# adc12.net
KiCad netlist of a schematic drawn in EAGLE
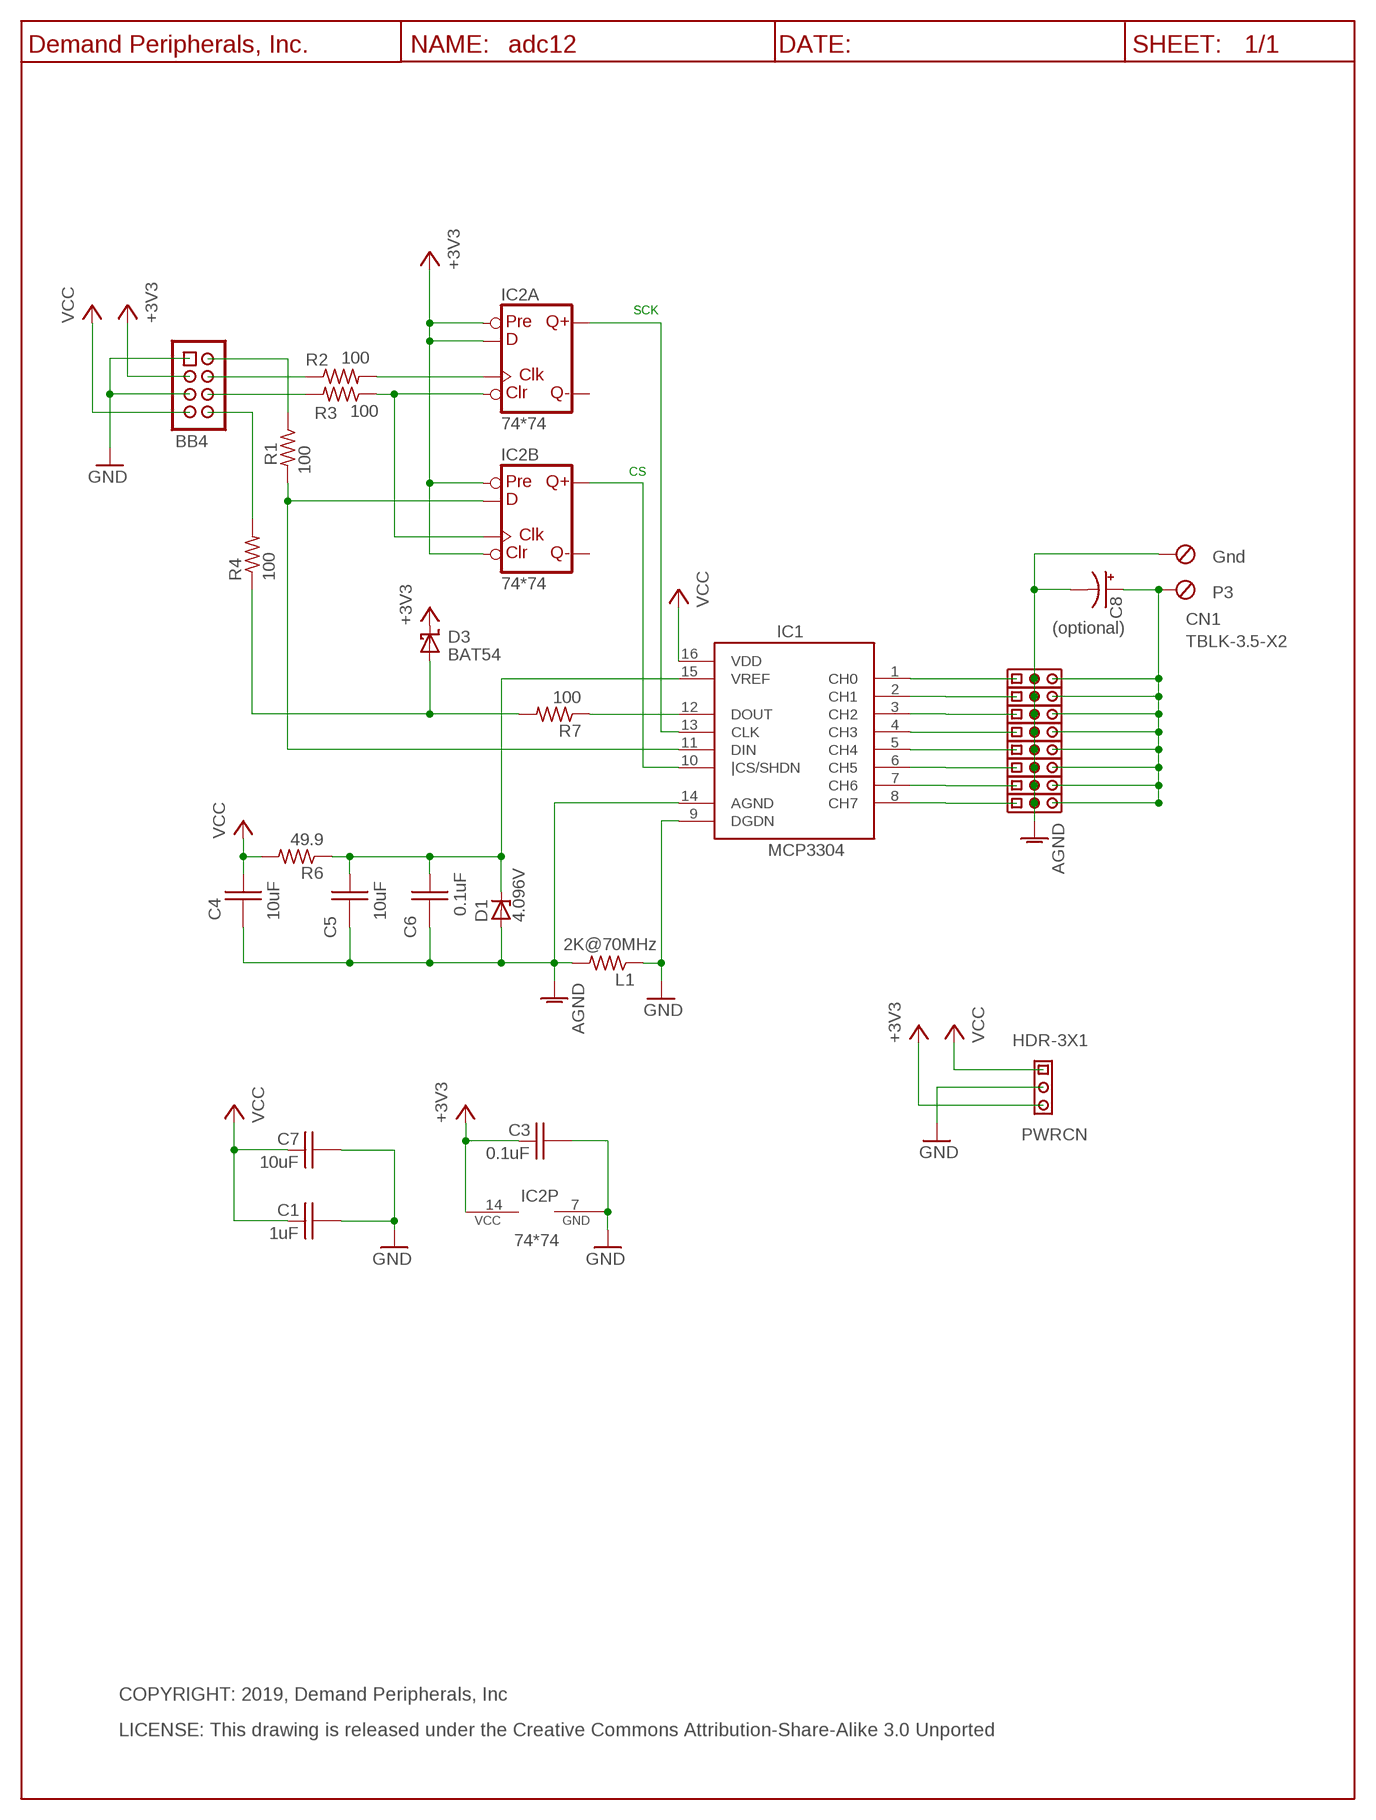
[diagram p0: schematic, sheet 1]

(export (version "E")
  (design (tool "Eeschema 10.0.6"))
  (components
    (comp (ref "BB4")
      (value "BB4_CON")
      (footprint "eagle-import:HDR-4X2")
      (libsource (lib "eagle-import") (part "HDR-4X2-SHR"))
    )
    (comp (ref "C1")
      (value "1uF")
      (footprint "eagle-import:C0603")
      (libsource (lib "eagle-import") (part "C1.0UF_C0603"))
    )
    (comp (ref "C3")
      (value "0.1uF")
      (footprint "eagle-import:C0603")
      (libsource (lib "eagle-import") (part "C0.1UF_C0603"))
    )
    (comp (ref "C4")
      (value "10uF")
      (footprint "eagle-import:C0805")
      (libsource (lib "eagle-import") (part "C10UF35V_C0805"))
    )
    (comp (ref "C5")
      (value "10uF")
      (footprint "eagle-import:C0805")
      (libsource (lib "eagle-import") (part "C10UF35V_C0805"))
    )
    (comp (ref "C6")
      (value "0.1uF")
      (footprint "eagle-import:C0603")
      (libsource (lib "eagle-import") (part "C0.1UF_C0603"))
    )
    (comp (ref "C7")
      (value "10uF")
      (footprint "eagle-import:C0805")
      (libsource (lib "eagle-import") (part "C10UF35V_C0805"))
    )
    (comp (ref "C8")
      (value "C100UF_E3.5-8")
      (footprint "eagle-import:E3.5-8")
      (libsource (lib "eagle-import") (part "C100UF_E3.5-8"))
    )
    (comp (ref "CN1")
      (value "TBLK-3.5-X2")
      (footprint "eagle-import:TBLK-3.5-X2")
      (libsource (lib "eagle-import") (part "TBLK-3.5-X2"))
    )
    (comp (ref "D1")
      (value "4.096V")
      (footprint "eagle-import:SOT23")
      (libsource (lib "eagle-import") (part "LM4040"))
    )
    (comp (ref "D3")
      (value "BAT54")
      (footprint "eagle-import:SOT23")
      (libsource (lib "eagle-import") (part "BAT54"))
    )
    (comp (ref "IC1")
      (value "MCP3304")
      (footprint "eagle-import:SO16")
      (libsource (lib "eagle-import") (part "MCP3304"))
    )
    (comp (ref "IC2")
      (value "74*74")
      (footprint "eagle-import:SO14")
      (libsource (lib "eagle-import") (part "74AHC74SS"))
    )
    (comp (ref "L1")
      (value "2K@70MHz")
      (footprint "eagle-import:R0805")
      (libsource (lib "eagle-import") (part "L2K70MHZR0805"))
    )
    (comp (ref "PWRCN")
      (value "HDR-3X1")
      (footprint "eagle-import:HDR-3X1")
      (libsource (lib "eagle-import") (part "HDR-3X1"))
    )
    (comp (ref "R1")
      (value "100")
      (footprint "eagle-import:R0603")
      (libsource (lib "eagle-import") (part "R100_R0603"))
    )
    (comp (ref "R2")
      (value "100")
      (footprint "eagle-import:R0603")
      (libsource (lib "eagle-import") (part "R100_R0603"))
    )
    (comp (ref "R3")
      (value "100")
      (footprint "eagle-import:R0603")
      (libsource (lib "eagle-import") (part "R100_R0603"))
    )
    (comp (ref "R4")
      (value "100")
      (footprint "eagle-import:R0603")
      (libsource (lib "eagle-import") (part "R100_R0603"))
    )
    (comp (ref "R6")
      (value "49.9")
      (footprint "eagle-import:R0603")
      (libsource (lib "eagle-import") (part "R49.9R0603"))
    )
    (comp (ref "R7")
      (value "100")
      (footprint "eagle-import:R0603")
      (libsource (lib "eagle-import") (part "R100_R0603"))
    )
    (comp (ref "U$3")
      (value "DP_FRAME_P")
      (footprint "eagle-import:LETTER_P")
      (libsource (lib "eagle-import") (part "DP_FRAME_P"))
    )
    (comp (ref "U$6")
      (value "HDR-3X1")
      (footprint "eagle-import:HDR-3X1")
      (libsource (lib "eagle-import") (part "HDR-3X1"))
    )
    (comp (ref "U$7")
      (value "HDR-3X1")
      (footprint "eagle-import:HDR-3X1")
      (libsource (lib "eagle-import") (part "HDR-3X1"))
    )
    (comp (ref "U$8")
      (value "HDR-3X1")
      (footprint "eagle-import:HDR-3X1")
      (libsource (lib "eagle-import") (part "HDR-3X1"))
    )
    (comp (ref "U$9")
      (value "HDR-3X1")
      (footprint "eagle-import:HDR-3X1")
      (libsource (lib "eagle-import") (part "HDR-3X1"))
    )
    (comp (ref "U$10")
      (value "HDR-3X1")
      (footprint "eagle-import:HDR-3X1")
      (libsource (lib "eagle-import") (part "HDR-3X1"))
    )
    (comp (ref "U$11")
      (value "HDR-3X1")
      (footprint "eagle-import:HDR-3X1")
      (libsource (lib "eagle-import") (part "HDR-3X1"))
    )
    (comp (ref "U$12")
      (value "HDR-3X1")
      (footprint "eagle-import:HDR-3X1")
      (libsource (lib "eagle-import") (part "HDR-3X1"))
    )
    (comp (ref "U$13")
      (value "HDR-3X1")
      (footprint "eagle-import:HDR-3X1")
      (libsource (lib "eagle-import") (part "HDR-3X1"))
    )
  )
  (nets
    (net (code "1") (name "+3V3") (class "Default")
      (node (ref "BB4") (pin "3") (pinfunction "3_3") (pintype "passive"))
      (node (ref "C3") (pin "1") (pinfunction "1_1") (pintype "passive"))
      (node (ref "D3") (pin "3") (pinfunction "CC_3") (pintype "passive"))
      (node (ref "IC2") (pin "10") (pinfunction "PRE_10") (pintype "input"))
      (node (ref "IC2") (pin "13") (pinfunction "CLR_13") (pintype "input"))
      (node (ref "IC2") (pin "14") (pinfunction "VCC_14") (pintype "power_in"))
      (node (ref "IC2") (pin "2") (pinfunction "D_2") (pintype "input"))
      (node (ref "IC2") (pin "4") (pinfunction "PRE_4") (pintype "input"))
      (node (ref "PWRCN") (pin "3") (pinfunction "3_3") (pintype "passive"))
    )
    (net (code "2") (name "AGND") (class "Default")
      (node (ref "C4") (pin "2") (pinfunction "2_2") (pintype "passive"))
      (node (ref "C5") (pin "2") (pinfunction "2_2") (pintype "passive"))
      (node (ref "C6") (pin "2") (pinfunction "2_2") (pintype "passive"))
      (node (ref "C8") (pin "-") (pinfunction "-_-") (pintype "passive"))
      (node (ref "CN1") (pin "1") (pinfunction "KL_1") (pintype "passive"))
      (node (ref "D1") (pin "2") (pinfunction "A_2") (pintype "passive"))
      (node (ref "IC1") (pin "14") (pinfunction "AGND_14") (pintype "bidirectional"))
      (node (ref "L1") (pin "2") (pinfunction "2_2") (pintype "passive"))
      (node (ref "U$10") (pin "2") (pinfunction "2_2") (pintype "passive"))
      (node (ref "U$11") (pin "2") (pinfunction "2_2") (pintype "passive"))
      (node (ref "U$12") (pin "2") (pinfunction "2_2") (pintype "passive"))
      (node (ref "U$13") (pin "2") (pinfunction "2_2") (pintype "passive"))
      (node (ref "U$6") (pin "2") (pinfunction "2_2") (pintype "passive"))
      (node (ref "U$7") (pin "2") (pinfunction "2_2") (pintype "passive"))
      (node (ref "U$8") (pin "2") (pinfunction "2_2") (pintype "passive"))
      (node (ref "U$9") (pin "2") (pinfunction "2_2") (pintype "passive"))
    )
    (net (code "3") (name "GND") (class "Default")
      (node (ref "BB4") (pin "1") (pinfunction "1_1") (pintype "passive"))
      (node (ref "BB4") (pin "5") (pinfunction "5_5") (pintype "passive"))
      (node (ref "C1") (pin "2") (pinfunction "2_2") (pintype "passive"))
      (node (ref "C3") (pin "2") (pinfunction "2_2") (pintype "passive"))
      (node (ref "C7") (pin "2") (pinfunction "2_2") (pintype "passive"))
      (node (ref "IC1") (pin "9") (pinfunction "DGDN_9") (pintype "bidirectional"))
      (node (ref "IC2") (pin "7") (pinfunction "GND_7") (pintype "power_in"))
      (node (ref "L1") (pin "1") (pinfunction "1_1") (pintype "passive"))
      (node (ref "PWRCN") (pin "2") (pinfunction "2_2") (pintype "passive"))
    )
    (net (code "4") (name "Net-(BB4-Pad2)") (class "Default")
      (node (ref "BB4") (pin "2") (pinfunction "2_2") (pintype "passive"))
      (node (ref "R1") (pin "1") (pinfunction "1_1") (pintype "passive"))
    )
    (net (code "5") (name "Net-(BB4-Pad4)") (class "Default")
      (node (ref "BB4") (pin "4") (pinfunction "4_4") (pintype "passive"))
      (node (ref "R2") (pin "1") (pinfunction "1_1") (pintype "passive"))
    )
    (net (code "6") (name "Net-(BB4-Pad6)") (class "Default")
      (node (ref "BB4") (pin "6") (pinfunction "6_6") (pintype "passive"))
      (node (ref "R3") (pin "2") (pinfunction "2_2") (pintype "passive"))
    )
    (net (code "7") (name "Net-(BB4-Pad8)") (class "Default")
      (node (ref "BB4") (pin "8") (pinfunction "8_8") (pintype "passive"))
      (node (ref "R4") (pin "2") (pinfunction "2_2") (pintype "passive"))
    )
    (net (code "8") (name "Net-(CN1-KL1)") (class "Default")
      (node (ref "C8") (pin "+") (pinfunction "+_+") (pintype "passive"))
      (node (ref "CN1") (pin "2") (pinfunction "KL1_2") (pintype "passive"))
      (node (ref "U$10") (pin "3") (pinfunction "3_3") (pintype "passive"))
      (node (ref "U$11") (pin "3") (pinfunction "3_3") (pintype "passive"))
      (node (ref "U$12") (pin "3") (pinfunction "3_3") (pintype "passive"))
      (node (ref "U$13") (pin "3") (pinfunction "3_3") (pintype "passive"))
      (node (ref "U$6") (pin "3") (pinfunction "3_3") (pintype "passive"))
      (node (ref "U$7") (pin "3") (pinfunction "3_3") (pintype "passive"))
      (node (ref "U$8") (pin "3") (pinfunction "3_3") (pintype "passive"))
      (node (ref "U$9") (pin "3") (pinfunction "3_3") (pintype "passive"))
    )
    (net (code "9") (name "Net-(D1-C)") (class "Default")
      (node (ref "C5") (pin "1") (pinfunction "1_1") (pintype "passive"))
      (node (ref "C6") (pin "1") (pinfunction "1_1") (pintype "passive"))
      (node (ref "D1") (pin "1") (pinfunction "C_1") (pintype "passive"))
      (node (ref "IC1") (pin "15") (pinfunction "VREF_15") (pintype "bidirectional"))
      (node (ref "R6") (pin "1") (pinfunction "1_1") (pintype "passive"))
    )
    (net (code "10") (name "Net-(D3-A)") (class "Default")
      (node (ref "D3") (pin "1") (pinfunction "A_1") (pintype "passive"))
      (node (ref "R4") (pin "1") (pinfunction "1_1") (pintype "passive"))
      (node (ref "R7") (pin "2") (pinfunction "2_2") (pintype "passive"))
    )
    (net (code "11") (name "Net-(IC1-CH0)") (class "Default")
      (node (ref "IC1") (pin "1") (pinfunction "CH0_1") (pintype "bidirectional"))
      (node (ref "U$13") (pin "1") (pinfunction "1_1") (pintype "passive"))
    )
    (net (code "12") (name "Net-(IC1-CH1)") (class "Default")
      (node (ref "IC1") (pin "2") (pinfunction "CH1_2") (pintype "bidirectional"))
      (node (ref "U$12") (pin "1") (pinfunction "1_1") (pintype "passive"))
    )
    (net (code "13") (name "Net-(IC1-CH2)") (class "Default")
      (node (ref "IC1") (pin "3") (pinfunction "CH2_3") (pintype "bidirectional"))
      (node (ref "U$11") (pin "1") (pinfunction "1_1") (pintype "passive"))
    )
    (net (code "14") (name "Net-(IC1-CH3)") (class "Default")
      (node (ref "IC1") (pin "4") (pinfunction "CH3_4") (pintype "bidirectional"))
      (node (ref "U$10") (pin "1") (pinfunction "1_1") (pintype "passive"))
    )
    (net (code "15") (name "Net-(IC1-CH4)") (class "Default")
      (node (ref "IC1") (pin "5") (pinfunction "CH4_5") (pintype "bidirectional"))
      (node (ref "U$9") (pin "1") (pinfunction "1_1") (pintype "passive"))
    )
    (net (code "16") (name "Net-(IC1-CH5)") (class "Default")
      (node (ref "IC1") (pin "6") (pinfunction "CH5_6") (pintype "bidirectional"))
      (node (ref "U$8") (pin "1") (pinfunction "1_1") (pintype "passive"))
    )
    (net (code "17") (name "Net-(IC1-CH6)") (class "Default")
      (node (ref "IC1") (pin "7") (pinfunction "CH6_7") (pintype "bidirectional"))
      (node (ref "U$7") (pin "1") (pinfunction "1_1") (pintype "passive"))
    )
    (net (code "18") (name "Net-(IC1-CH7)") (class "Default")
      (node (ref "IC1") (pin "8") (pinfunction "CH7_8") (pintype "bidirectional"))
      (node (ref "U$6") (pin "1") (pinfunction "1_1") (pintype "passive"))
    )
    (net (code "19") (name "Net-(IC1-CLK)") (class "Default")
      (node (ref "IC1") (pin "13") (pinfunction "CLK_13") (pintype "bidirectional"))
      (node (ref "IC2") (pin "5") (pinfunction "Q_5") (pintype "output"))
    )
    (net (code "20") (name "Net-(IC1-DIN)") (class "Default")
      (node (ref "IC1") (pin "11") (pinfunction "DIN_11") (pintype "bidirectional"))
      (node (ref "IC2") (pin "12") (pinfunction "D_12") (pintype "input"))
      (node (ref "R1") (pin "2") (pinfunction "2_2") (pintype "passive"))
    )
    (net (code "21") (name "Net-(IC1-DOUT)") (class "Default")
      (node (ref "IC1") (pin "12") (pinfunction "DOUT_12") (pintype "bidirectional"))
      (node (ref "R7") (pin "1") (pinfunction "1_1") (pintype "passive"))
    )
    (net (code "22") (name "Net-(IC1-|CS{slash}SHDN)") (class "Default")
      (node (ref "IC1") (pin "10") (pinfunction "|CS/SHDN_10") (pintype "bidirectional"))
      (node (ref "IC2") (pin "9") (pinfunction "Q_9") (pintype "output"))
    )
    (net (code "23") (name "Net-(IC2A-CLK)") (class "Default")
      (node (ref "IC2") (pin "3") (pinfunction "CLK_3") (pintype "input"))
      (node (ref "R2") (pin "2") (pinfunction "2_2") (pintype "passive"))
    )
    (net (code "24") (name "Net-(IC2A-CLR)") (class "Default")
      (node (ref "IC2") (pin "1") (pinfunction "CLR_1") (pintype "input"))
      (node (ref "IC2") (pin "11") (pinfunction "CLK_11") (pintype "input"))
      (node (ref "R3") (pin "1") (pinfunction "1_1") (pintype "passive"))
    )
    (net (code "25") (name "VCC") (class "Default")
      (node (ref "BB4") (pin "7") (pinfunction "7_7") (pintype "passive"))
      (node (ref "C1") (pin "1") (pinfunction "1_1") (pintype "passive"))
      (node (ref "C4") (pin "1") (pinfunction "1_1") (pintype "passive"))
      (node (ref "C7") (pin "1") (pinfunction "1_1") (pintype "passive"))
      (node (ref "IC1") (pin "16") (pinfunction "VDD_16") (pintype "bidirectional"))
      (node (ref "PWRCN") (pin "1") (pinfunction "1_1") (pintype "passive"))
      (node (ref "R6") (pin "2") (pinfunction "2_2") (pintype "passive"))
    )
    (net (code "26") (name "unconnected-(IC2A-~{Q}-Pad6)") (class "Default")
      (node (ref "IC2") (pin "6") (pinfunction "~{Q}_6") (pintype "output"))
    )
    (net (code "27") (name "unconnected-(IC2B-~{Q}-Pad8)") (class "Default")
      (node (ref "IC2") (pin "8") (pinfunction "~{Q}_8") (pintype "output"))
    )
  )
)
